# MCU.net
KiCad netlist of a schematic drawn in Altium Designer
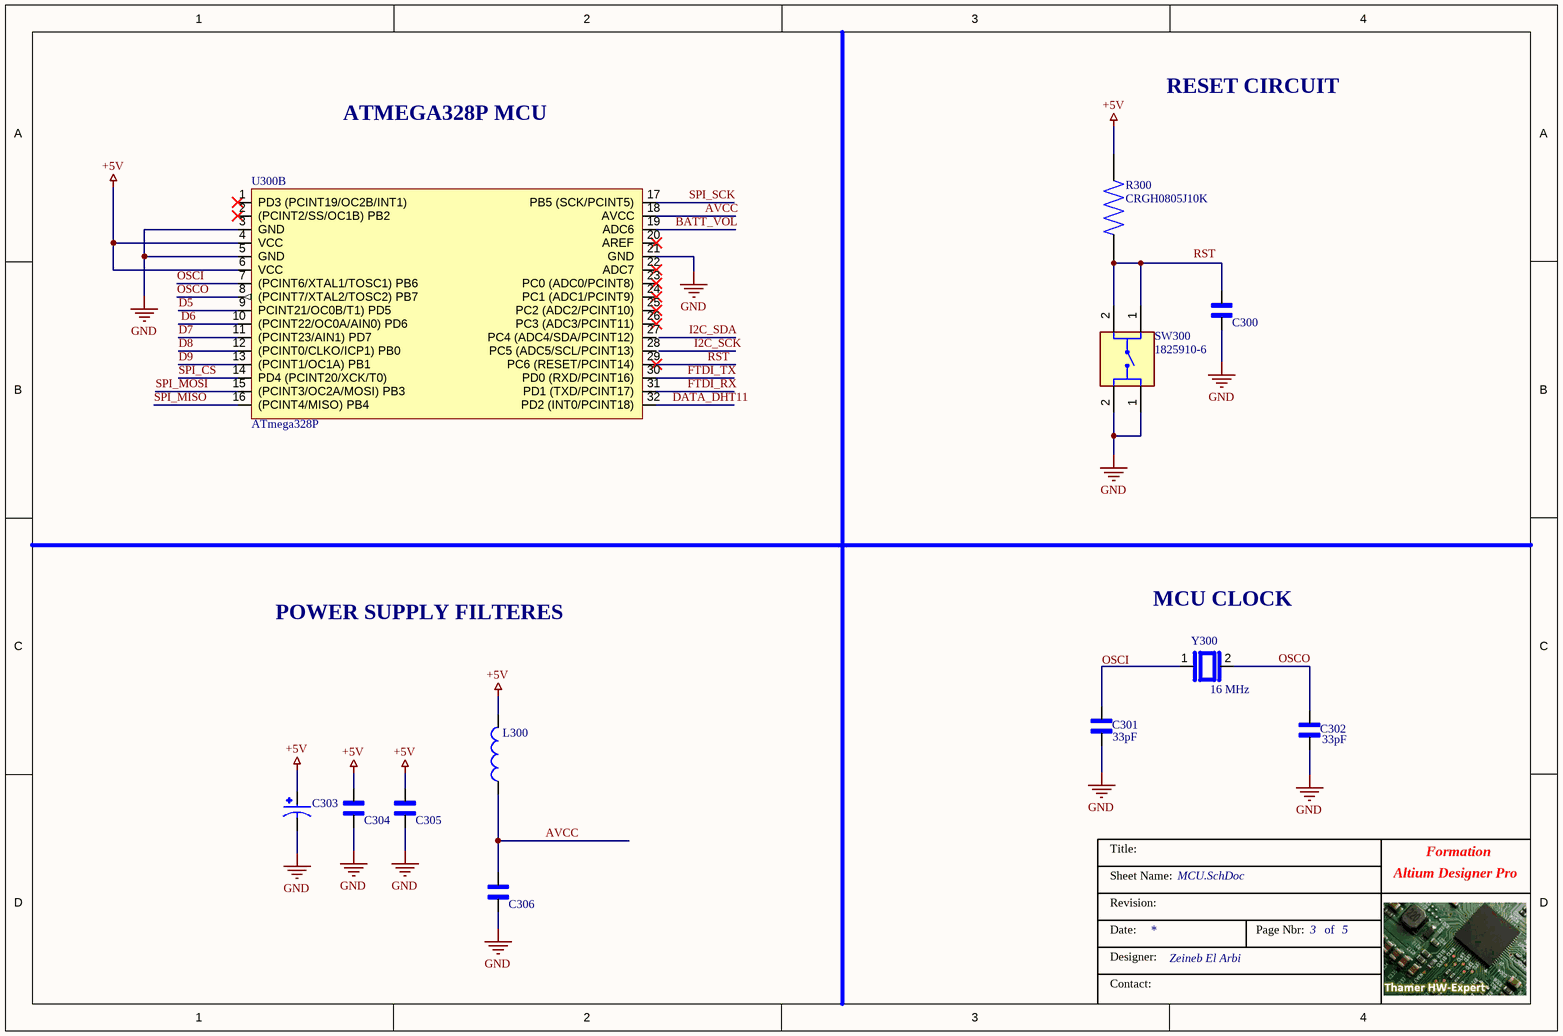
[diagram p0: MCU.SchDoc]

(export (version "E")
  (design (tool "Eeschema 10.0.6"))
  (components
    (comp (ref "C300")
      (value "GCM21BR71H104KA37K")
      (footprint "CAPC2012X135N")
      (description ".1UF 50V 10% 080")
      (fields (field (name "MF") "{'manufacturer': u'Murata'}"))
      (libsource (lib "") (part "GCM21BR71H104KA37K_1"))
    )
    (comp (ref "C301")
      (value "33pF")
      (footprint "CAPC2012X100N")
      (description "Cap Ceramic 33pF 250V C0G 5% Pad SMD 0805 125C T/R")
      (fields (field (name "MF") "{'manufacturer': u'Murata'}") (field (name "MP") "GRM21A5C2E330JW01D"))
      (libsource (lib "Capacitor") (part "GRM21A5C2E330JW01D"))
    )
    (comp (ref "C302")
      (value "33pF")
      (footprint "CAPC2012X100N")
      (description "Cap Ceramic 33pF 250V C0G 5% Pad SMD 0805 125C T/R")
      (fields (field (name "MF") "{'manufacturer': u'Murata'}") (field (name "MP") "GRM21A5C2E330JW01D"))
      (libsource (lib "Capacitor") (part "GRM21A5C2E330JW01D"))
    )
    (comp (ref "C303")
      (value "EEEHB1H4R7AR")
      (footprint "CAP_EEEHB1H4R7AR")
      (fields (field (name "MF") "{'manufacturer': u'Panasonic'}"))
      (libsource (lib "Capacitor") (part "EEEHB1H4R7AR"))
    )
    (comp (ref "C304")
      (value "GCM21BR71H104KA37K")
      (footprint "CAPC2012X135N")
      (description ".1UF 50V 10% 080")
      (fields (field (name "MF") "{'manufacturer': u'Murata'}"))
      (libsource (lib "Capacitor") (part "GCM21BR71H104KA37K"))
    )
    (comp (ref "C305")
      (value "GCM21BR71H104KA37K")
      (footprint "CAPC2012X135N")
      (description ".1UF 50V 10% 080")
      (fields (field (name "MF") "{'manufacturer': u'Murata'}"))
      (libsource (lib "Capacitor") (part "GCM21BR71H104KA37K"))
    )
    (comp (ref "C306")
      (value "GCM21BR71H104KA37K")
      (footprint "CAPC2012X135N")
      (description ".1UF 50V 10% 080")
      (fields (field (name "MF") "{'manufacturer': u'Murata'}"))
      (libsource (lib "Capacitor") (part "GCM21BR71H104KA37K"))
    )
    (comp (ref "L300")
      (value "LQM21DN100N00D")
      (footprint "INDC2012X105N")
      (description "Power inductor SMD 0805 10uH")
      (fields (field (name "MF") "{'manufacturer': u'Murata'}"))
      (libsource (lib "Inductors") (part "LQM21DN100N00D"))
    )
    (comp (ref "R300")
      (value "CRGH0805J10K")
      (footprint "RESC2012X65N")
      (description "Res Thick Film 0805 10K Ohm 5% 1/3W Â±100ppm/Â°C Molded SMD SMD T/R")
      (fields (field (name "MF") "{'manufacturer': u'TE Connectivity'}"))
      (libsource (lib "Resistor") (part "CRGH0805J10K"))
    )
    (comp (ref "SW300")
      (value "1825910-6")
      (footprint "SW_1825910-6-4")
      (description "Switch Tactile OFF (ON) SPST Round Button PC Pins 0.05A 24VDC 100000Cycles 1.57N Thru-Hole Loose")
      (fields (field (name "MF") "{'manufacturer': u'TE Connectivity'}"))
      (libsource (lib "1825910-6") (part "1825910-6"))
    )
    (comp (ref "U300")
      (value "ATmega328P")
      (footprint "TQFP80P900X900X120-32N")
      (description "8-bit AVR Microcontroller with 32K Bytes In-System\r\nProgrammable Flash")
      (libsource (lib "sch_Library") (part "ATmega328P"))
    )
    (comp (ref "Y300")
      (value "16 MHz")
      (footprint "XTAL_HC49P488W43L1150T466H350")
      (description "HC49US Series 16 MHz Â±30 ppm 18 pF -20 to +70 Â°C Through Hole AT-CUT Crystal")
      (fields
        (field (name "MF") "{'manufacturer': u'Citizen Finedevice Co Ltd'}")
        (field (name "MP") "HC-49/U-S16000000ABJB")
      )
      (libsource (lib "Quartz") (part "HC-49/U-S16000000ABJB"))
    )
  )
  (nets
    (net (code "1") (name "+5V") (class "Default")
      (node (ref "C303") (pin "1") (pinfunction "1_1") (pintype "passive"))
      (node (ref "C304") (pin "1") (pinfunction "1_1") (pintype "passive"))
      (node (ref "C305") (pin "1") (pinfunction "1_1") (pintype "passive"))
      (node (ref "L300") (pin "2") (pinfunction "2_2") (pintype "passive"))
      (node (ref "R300") (pin "2") (pinfunction "2_2") (pintype "passive"))
      (node (ref "U300") (pin "4") (pinfunction "VCC_4") (pintype "power_in"))
      (node (ref "U300") (pin "6") (pinfunction "VCC_6") (pintype "power_in"))
    )
    (net (code "3") (name "/AVCC") (class "Default")
      (node (ref "C306") (pin "1") (pinfunction "1_1") (pintype "passive"))
      (node (ref "L300") (pin "1") (pinfunction "1_1") (pintype "passive"))
      (node (ref "U300") (pin "18") (pinfunction "AVCC_18") (pintype "power_in"))
    )
    (net (code "4") (name "/BATT_VOL") (class "Default")
      (node (ref "U300") (pin "19") (pinfunction "ADC6_19") (pintype "bidirectional"))
    )
    (net (code "5") (name "/D5") (class "Default")
      (node (ref "U300") (pin "9") (pinfunction "PCINT21/OC0B/T1)_PD5_9") (pintype "bidirectional"))
    )
    (net (code "6") (name "/D6") (class "Default")
      (node (ref "U300") (pin "10") (pinfunction "(PCINT22/OC0A/AIN0)_PD6_10") (pintype "bidirectional"))
    )
    (net (code "7") (name "/D7") (class "Default")
      (node (ref "U300") (pin "11") (pinfunction "(PCINT23/AIN1)_PD7_11") (pintype "bidirectional"))
    )
    (net (code "8") (name "/D8") (class "Default")
      (node (ref "U300") (pin "12") (pinfunction "(PCINT0/CLKO/ICP1)_PB0_12") (pintype "bidirectional"))
    )
    (net (code "9") (name "/D9") (class "Default")
      (node (ref "U300") (pin "13") (pinfunction "(PCINT1/OC1A)_PB1_13") (pintype "bidirectional"))
    )
    (net (code "10") (name "/DATA_DHT11") (class "Default")
      (node (ref "U300") (pin "32") (pinfunction "__PD2_(INT0/PCINT18)_32") (pintype "bidirectional"))
    )
    (net (code "11") (name "/FTDI_RX") (class "Default")
      (node (ref "U300") (pin "31") (pinfunction "_PD1_(TXD/PCINT17)_31") (pintype "bidirectional"))
    )
    (net (code "12") (name "/FTDI_TX") (class "Default")
      (node (ref "U300") (pin "30") (pinfunction "PD0_(RXD/PCINT16)_30") (pintype "bidirectional"))
    )
    (net (code "15") (name "/OSCI") (class "Default")
      (node (ref "C301") (pin "2") (pinfunction "2_2") (pintype "passive"))
      (node (ref "U300") (pin "7") (pinfunction "(PCINT6/XTAL1/TOSC1)_PB6_7") (pintype "passive"))
      (node (ref "Y300") (pin "1") (pinfunction "1_1") (pintype "passive"))
    )
    (net (code "16") (name "/OSCO") (class "Default")
      (node (ref "C302") (pin "2") (pinfunction "2_2") (pintype "passive"))
      (node (ref "U300") (pin "8") (pinfunction "(PCINT7/XTAL2/TOSC2)_PB7_8") (pintype "output"))
      (node (ref "Y300") (pin "2") (pinfunction "2_2") (pintype "passive"))
    )
    (net (code "17") (name "/RST") (class "Default")
      (node (ref "U300") (pin "29") (pinfunction "PC6_(RESET/PCINT14)_29") (pintype "bidirectional+no_connect"))
    )
    (net (code "18") (name "/SPI_CS") (class "Default")
      (node (ref "U300") (pin "14") (pinfunction "PD4_(PCINT20/XCK/T0)_14") (pintype "bidirectional"))
    )
    (net (code "19") (name "/SPI_MISO") (class "Default")
      (node (ref "U300") (pin "16") (pinfunction "(PCINT4/MISO)_PB4_16") (pintype "passive"))
    )
    (net (code "20") (name "/SPI_MOSI") (class "Default")
      (node (ref "U300") (pin "15") (pinfunction "(PCINT3/OC2A/MOSI)_PB3_15") (pintype "bidirectional"))
    )
    (net (code "21") (name "/SPI_SCK") (class "Default")
      (node (ref "U300") (pin "17") (pinfunction "PB5_(SCK/PCINT5)_17") (pintype "bidirectional"))
    )
    (net (code "22") (name "GND") (class "Default")
      (node (ref "C300") (pin "1") (pinfunction "1_1") (pintype "passive"))
      (node (ref "C301") (pin "1") (pinfunction "1_1") (pintype "passive"))
      (node (ref "C302") (pin "1") (pinfunction "1_1") (pintype "passive"))
      (node (ref "C303") (pin "2") (pinfunction "2_2") (pintype "passive"))
      (node (ref "C304") (pin "2") (pinfunction "2_2") (pintype "passive"))
      (node (ref "C305") (pin "2") (pinfunction "2_2") (pintype "passive"))
      (node (ref "C306") (pin "2") (pinfunction "2_2") (pintype "passive"))
      (node (ref "SW300") (pin "1") (pinfunction "1_1") (pintype "passive"))
      (node (ref "SW300") (pin "2") (pinfunction "2_2") (pintype "passive"))
      (node (ref "U300") (pin "21") (pinfunction "GND_21") (pintype "power_in"))
      (node (ref "U300") (pin "3") (pinfunction "GND_3") (pintype "power_in"))
      (node (ref "U300") (pin "5") (pinfunction "GND_5") (pintype "power_in"))
    )
    (net (code "23") (name "Net-(C300-Pad1)") (class "Default")
      (node (ref "C300") (pin "1") (pinfunction "1_1") (pintype "passive"))
      (node (ref "R300") (pin "1") (pinfunction "1_1") (pintype "passive"))
      (node (ref "SW300") (pin "1") (pinfunction "1_1") (pintype "passive"))
      (node (ref "SW300") (pin "2") (pinfunction "2_2") (pintype "passive"))
    )
    (net (code "24") (name "unconnected-(U300B-(PCINT2{slash}SS{slash}OC1B)_PB2-Pad2)") (class "Default")
      (node (ref "U300") (pin "2") (pinfunction "(PCINT2/SS/OC1B)_PB2_2") (pintype "bidirectional+no_connect"))
    )
    (net (code "25") (name "unconnected-(U300B-ADC7-Pad22)") (class "Default")
      (node (ref "U300") (pin "22") (pinfunction "ADC7_22") (pintype "bidirectional+no_connect"))
    )
    (net (code "26") (name "unconnected-(U300B-AREF-Pad20)") (class "Default")
      (node (ref "U300") (pin "20") (pinfunction "AREF_20") (pintype "power_in+no_connect"))
    )
    (net (code "27") (name "unconnected-(U300B-PC0_(ADC0{slash}PCINT8)-Pad23)") (class "Default")
      (node (ref "U300") (pin "23") (pinfunction "PC0_(ADC0/PCINT8)_23") (pintype "bidirectional+no_connect"))
    )
    (net (code "28") (name "unconnected-(U300B-PC1_(ADC1{slash}PCINT9)-Pad24)") (class "Default")
      (node (ref "U300") (pin "24") (pinfunction "PC1_(ADC1/PCINT9)_24") (pintype "bidirectional+no_connect"))
    )
    (net (code "29") (name "unconnected-(U300B-PC2_(ADC2{slash}PCINT10)-Pad25)") (class "Default")
      (node (ref "U300") (pin "25") (pinfunction "PC2_(ADC2/PCINT10)_25") (pintype "bidirectional+no_connect"))
    )
    (net (code "30") (name "unconnected-(U300B-PC3_(ADC3{slash}PCINT11)-Pad26)") (class "Default")
      (node (ref "U300") (pin "26") (pinfunction "PC3_(ADC3/PCINT11)_26") (pintype "bidirectional+no_connect"))
    )
    (net (code "31") (name "unconnected-(U300B-PC4_(ADC4{slash}SDA{slash}PCINT12)-Pad27)") (class "Default")
      (node (ref "U300") (pin "27") (pinfunction "PC4_(ADC4/SDA/PCINT12)_27") (pintype "bidirectional"))
    )
    (net (code "32") (name "unconnected-(U300B-PC5_(ADC5{slash}SCL{slash}PCINT13)-Pad28)") (class "Default")
      (node (ref "U300") (pin "28") (pinfunction "PC5_(ADC5/SCL/PCINT13)_28") (pintype "bidirectional"))
    )
    (net (code "33") (name "unconnected-(U300B-PD3_(PCINT19{slash}OC2B{slash}INT1)-Pad1)") (class "Default")
      (node (ref "U300") (pin "1") (pinfunction "PD3_(PCINT19/OC2B/INT1)_1") (pintype "bidirectional+no_connect"))
    )
  )
)
